# Fri3d_2024_Blaster_00.net
KiCad netlist of a schematic drawn in Altium Designer
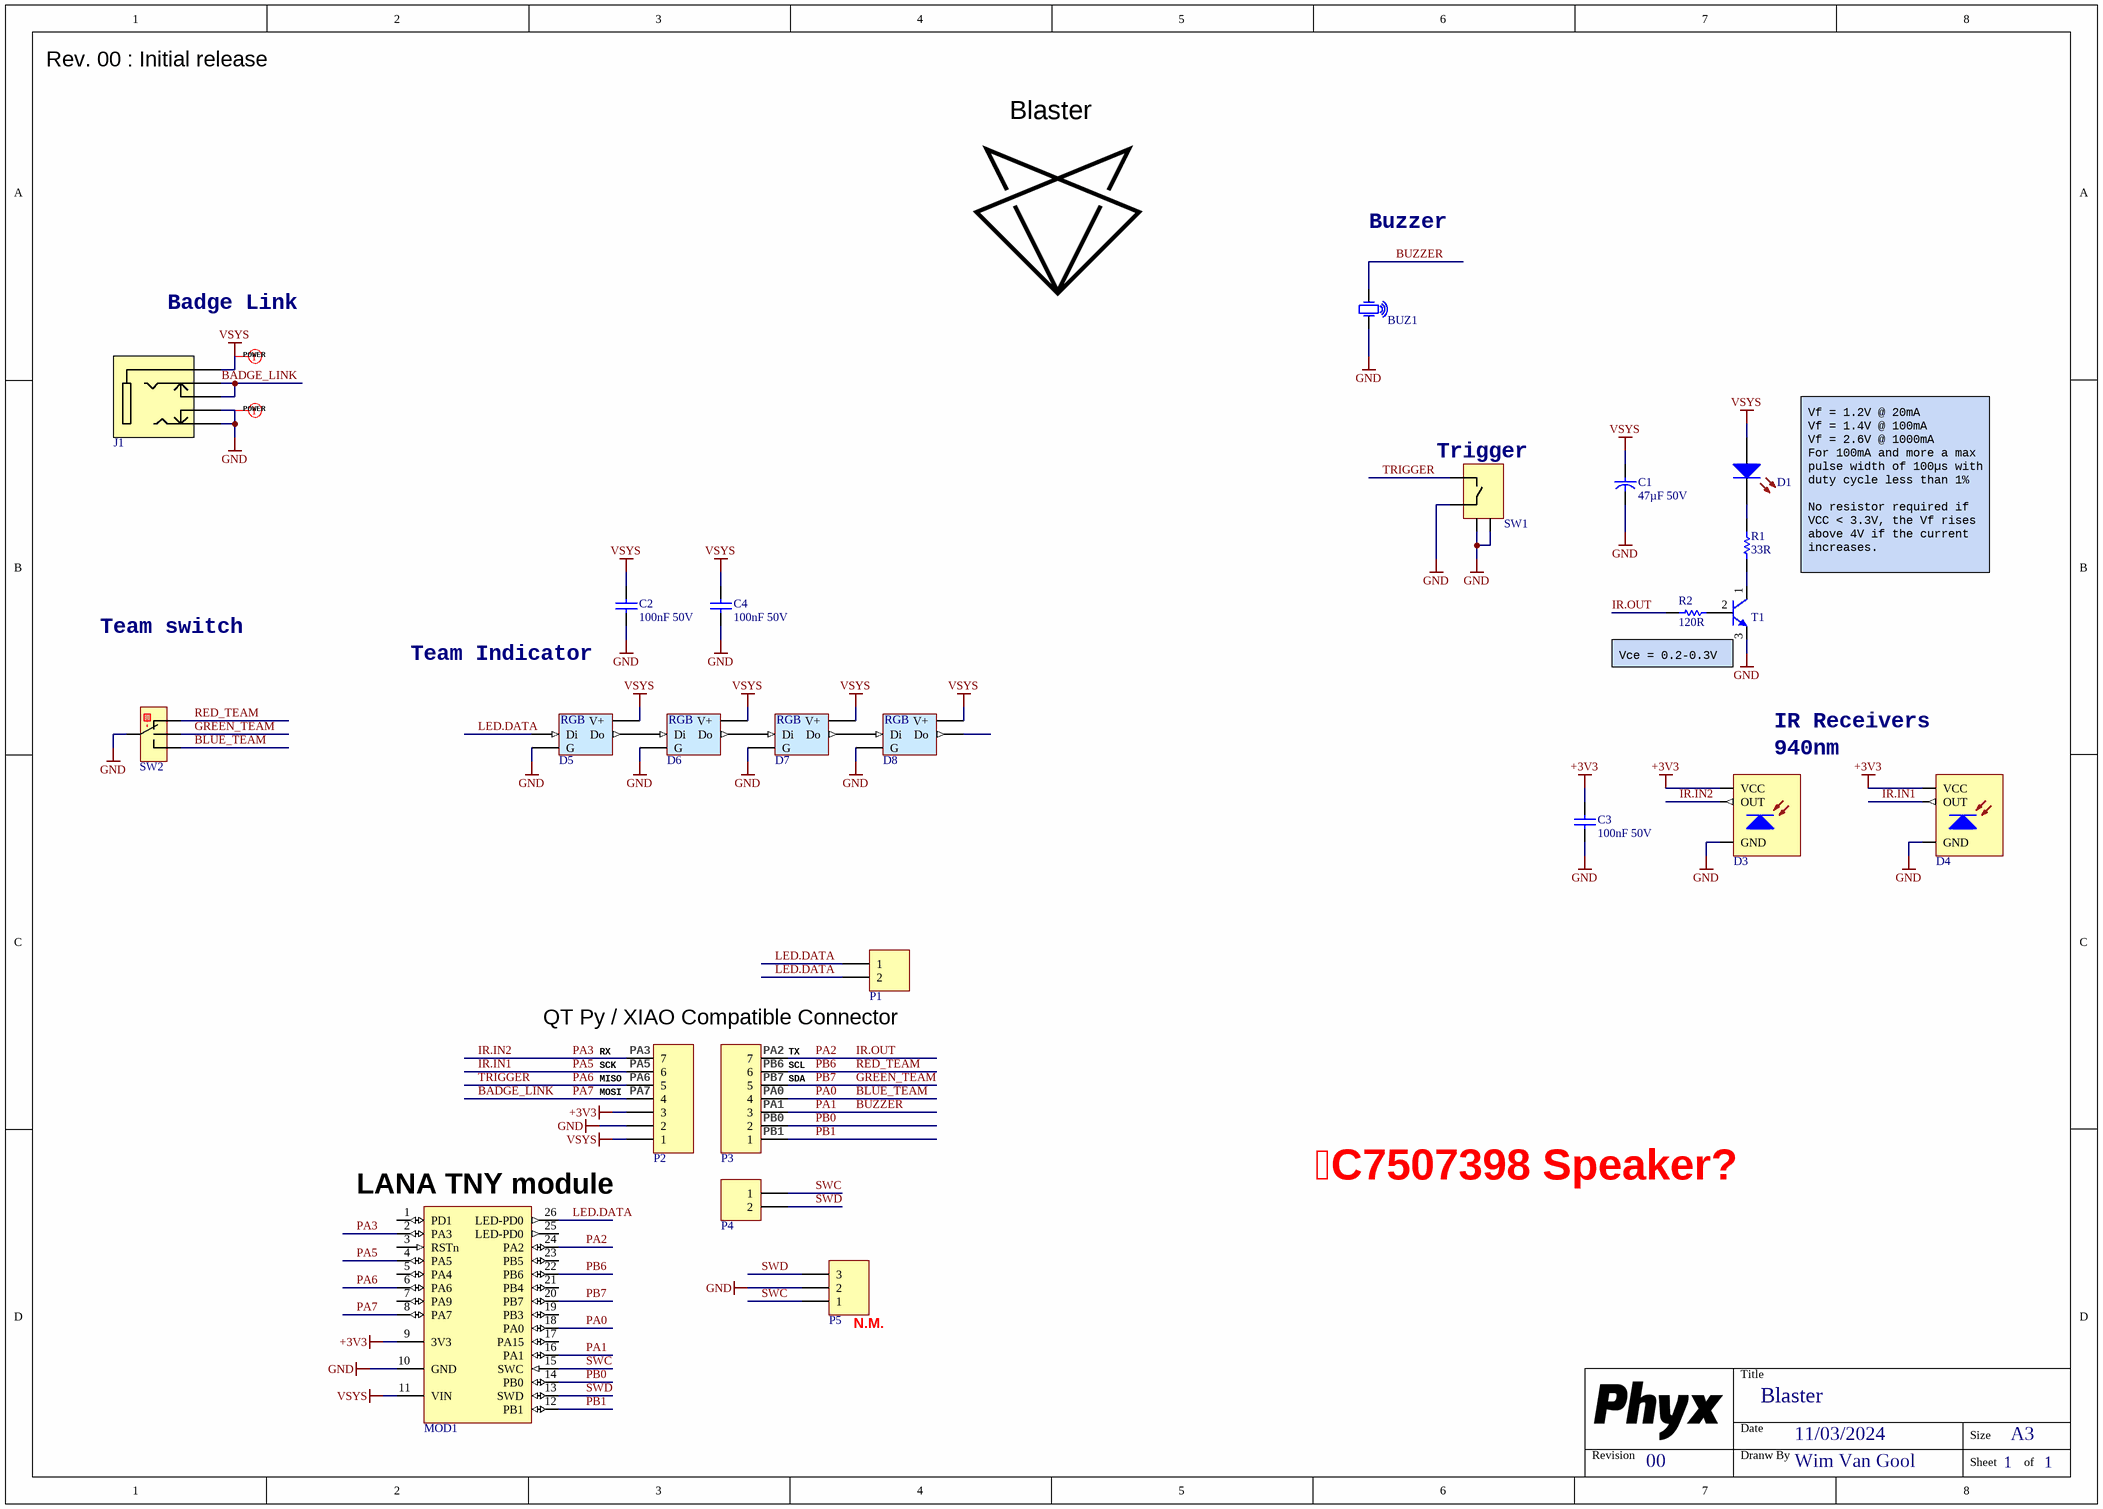
[diagram p0: Fri3d_2024_Blaster_00.SchDoc]

(export (version "E")
  (design (tool "Eeschema 10.0.6"))
  (components
    (comp (ref "BUZ1")
      (value "14x14x7mm Piezo Buzzer Transducer 80dB")
      (footprint "CUI_CEP-1162")
      (description "Crystal Oscillator")
      (libsource (lib "Phyx_Components") (part "Buzzer"))
    )
    (comp (ref "C1")
      (value "47µF 50V")
      (footprint "C_8x9_3.5mm")
      (description "Capacitor electrolyt")
      (fields (field (name "Comment") "CAP_POL"))
      (libsource (lib "Phyx_Components") (part "CAP_POL"))
    )
    (comp (ref "C2")
      (value "100nF 50V")
      (footprint "C_5.08mm")
      (description "Capacitor Ceramic")
      (fields (field (name "Comment") "CAP_CERAMIC"))
      (libsource (lib "Phyx_Components") (part "CAP_CERAMIC"))
    )
    (comp (ref "C3")
      (value "100nF 50V")
      (footprint "C_5.08mm")
      (description "Capacitor Ceramic")
      (fields (field (name "Comment") "CAP_CERAMIC"))
      (libsource (lib "Phyx_Components") (part "CAP_CERAMIC"))
    )
    (comp (ref "C4")
      (value "100nF 50V")
      (footprint "C_5.08mm")
      (description "Capacitor Ceramic")
      (fields (field (name "Comment") "CAP_CERAMIC"))
      (libsource (lib "Phyx_Components") (part "CAP_CERAMIC"))
    )
    (comp (ref "D1")
      (value "5mm IR LED, 940nm, 100mA, 1.35V, 25Deg")
      (footprint "LED_5MM_RD")
      (description "=Description")
      (libsource (lib "Phyx_Components") (part "LED_IR"))
    )
    (comp (ref "D3")
      (value "IRM-3638N3F14 Infrared Receiver 38 kHz 45° 2.7-5.5V")
      (footprint "VIS_TSOP381x_BENT")
      (description "=Description")
      (libsource (lib "Phyx_Components") (part "PHO_IR_TSOP381x"))
    )
    (comp (ref "D4")
      (value "IRM-3638N3F14 Infrared Receiver 38 kHz 45° 2.7-5.5V")
      (footprint "VIS_TSOP381x_BENT")
      (description "=Description")
      (libsource (lib "Phyx_Components") (part "PHO_IR_TSOP381x"))
    )
    (comp (ref "D5")
      (value "WS2812 based digital RGB LED 4020 White package Side emitting")
      (footprint "LED_8mm_RGB_RA")
      (description "=Description")
      (libsource (lib "Phyx_Components") (part "LED_RGB_WS2812B_5mm"))
    )
    (comp (ref "D6")
      (value "WS2812 based digital RGB LED 4020 White package Side emitting")
      (footprint "LED_8mm_RGB_RA")
      (description "=Description")
      (libsource (lib "Phyx_Components") (part "LED_RGB_WS2812B_5mm"))
    )
    (comp (ref "D7")
      (value "WS2812 based digital RGB LED 4020 White package Side emitting")
      (footprint "LED_8mm_RGB_RA")
      (description "=Description")
      (libsource (lib "Phyx_Components") (part "LED_RGB_WS2812B_5mm"))
    )
    (comp (ref "D8")
      (value "WS2812 based digital RGB LED 4020 White package Side emitting")
      (footprint "LED_8mm_RGB_RA")
      (description "=Description")
      (libsource (lib "Phyx_Components") (part "LED_RGB_WS2812B_5mm"))
    )
    (comp (ref "J1")
      (value "3.5mm jack, dual switch, black, 3 contacts")
      (footprint "CUI_SJ1-3525NG")
      (description "=Description")
      (libsource (lib "Phyx_Components") (part "CUI_SJ1-3525NG"))
    )
    (comp (ref "MOD1")
      (value "CH23V203 based TNY module")
      (footprint "PHYX_LANA_TNY_SMD")
      (libsource (lib "Phyx_Components") (part "PHYX_LANA_TNY_SMD"))
    )
    (comp (ref "P1") (value "Header 2") (footprint "HDR1X2") (libsource (lib "") (part "Header 2_1")))
    (comp (ref "P2")
      (value "Header 7")
      (footprint "HDR1X7")
      (libsource (lib "Phyx_Components") (part "Header 7"))
    )
    (comp (ref "P3") (value "Header 7") (footprint "HDR1X7") (libsource (lib "") (part "Header 7_1")))
    (comp (ref "P4")
      (value "Header 2")
      (footprint "HDR1X2")
      (libsource (lib "Phyx_Components") (part "Header 2"))
    )
    (comp (ref "P5")
      (value "Header 3")
      (footprint "HDR1X3")
      (libsource (lib "Phyx_Components") (part "Header 3"))
    )
    (comp (ref "R1")
      (value "33R")
      (footprint "RES_10mm")
      (fields (field (name "Comment") "RESISTOR"))
      (libsource (lib "Phyx_Components") (part "RESISTOR"))
    )
    (comp (ref "R2")
      (value "120R")
      (footprint "RES_10mm")
      (fields (field (name "Comment") "RESISTOR"))
      (libsource (lib "Phyx_Components") (part "RESISTOR"))
    )
    (comp (ref "SW1")
      (value "Tact switch, RA, 3,85mm")
      (footprint "TACTSW_RA_385")
      (libsource (lib "Phyx_Components") (part "SW_TACT_RA"))
    )
    (comp (ref "SW2")
      (value "1P3T SK13D07VG3 3mm post")
      (footprint "SK13D07VG3")
      (libsource (lib "Phyx_Components") (part "SW_1P3T"))
    )
    (comp (ref "T1")
      (value "0.2A 40V 100hfe NPN Transistor")
      (footprint "TO-92A_WIDE")
      (libsource (lib "Phyx_Components") (part "NPN_EBC"))
    )
  )
  (nets
    (net (code "1") (name "+3V3") (class "Default")
      (node (ref "C3") (pin "1") (pinfunction "1_1") (pintype "passive"))
      (node (ref "D3") (pin "3") (pinfunction "VCC_3") (pintype "power_in"))
      (node (ref "D4") (pin "3") (pinfunction "VCC_3") (pintype "power_in"))
      (node (ref "MOD1") (pin "9") (pinfunction "3V3_9") (pintype "power_in"))
      (node (ref "P2") (pin "3") (pinfunction "3_3") (pintype "passive"))
    )
    (net (code "3") (name "/BADGE_LINK") (class "Default")
      (node (ref "J1") (pin "3") (pinfunction "Ring_3") (pintype "passive"))
      (node (ref "J1") (pin "5") (pinfunction "5_5") (pintype "passive"))
      (node (ref "MOD1") (pin "8") (pinfunction "PA7_8") (pintype "bidirectional"))
      (node (ref "P2") (pin "4") (pinfunction "4_4") (pintype "passive"))
    )
    (net (code "4") (name "/BLUE_TEAM") (class "Default")
      (node (ref "MOD1") (pin "18") (pinfunction "PA0_18") (pintype "bidirectional"))
      (node (ref "P3") (pin "4") (pinfunction "4_4") (pintype "passive"))
      (node (ref "SW2") (pin "4") (pinfunction "4_4") (pintype "passive"))
    )
    (net (code "5") (name "/BUZZER") (class "Default")
      (node (ref "BUZ1") (pin "2") (pinfunction "OSC2_2") (pintype "passive"))
      (node (ref "MOD1") (pin "16") (pinfunction "PA1_16") (pintype "bidirectional"))
      (node (ref "P3") (pin "3") (pinfunction "3_3") (pintype "passive"))
    )
    (net (code "6") (name "/GREEN_TEAM") (class "Default")
      (node (ref "MOD1") (pin "20") (pinfunction "PB7_20") (pintype "bidirectional"))
      (node (ref "P3") (pin "5") (pinfunction "5_5") (pintype "passive"))
      (node (ref "SW2") (pin "2") (pinfunction "2_2") (pintype "passive"))
    )
    (net (code "7") (name "/IR.IN1") (class "Default")
      (node (ref "D4") (pin "1") (pinfunction "OUT_1") (pintype "output"))
      (node (ref "MOD1") (pin "4") (pinfunction "PA5_4") (pintype "bidirectional"))
      (node (ref "P2") (pin "6") (pinfunction "6_6") (pintype "passive"))
    )
    (net (code "8") (name "/IR.IN2") (class "Default")
      (node (ref "D3") (pin "1") (pinfunction "OUT_1") (pintype "output"))
      (node (ref "MOD1") (pin "2") (pinfunction "PA3_2") (pintype "bidirectional"))
      (node (ref "P2") (pin "7") (pinfunction "7_7") (pintype "passive"))
    )
    (net (code "9") (name "/IR.OUT") (class "Default")
      (node (ref "MOD1") (pin "24") (pinfunction "PA2_24") (pintype "bidirectional"))
      (node (ref "P3") (pin "7") (pinfunction "7_7") (pintype "passive"))
      (node (ref "R2") (pin "2") (pinfunction "2_2") (pintype "passive"))
    )
    (net (code "10") (name "/LED.DATA") (class "Default")
      (node (ref "D5") (pin "4") (pinfunction "Di_4") (pintype "input"))
      (node (ref "MOD1") (pin "26") (pinfunction "LED-PD0_26") (pintype "output"))
      (node (ref "P1") (pin "1") (pinfunction "1_1") (pintype "passive"))
      (node (ref "P1") (pin "2") (pinfunction "2_2") (pintype "passive"))
    )
    (net (code "11") (name "/PA6") (class "Default")
      (node (ref "MOD1") (pin "6") (pinfunction "PA6_6") (pintype "bidirectional"))
      (node (ref "P2") (pin "5") (pinfunction "5_5") (pintype "passive"))
      (node (ref "SW1") (pin "1") (pinfunction "1_1") (pintype "passive"))
    )
    (net (code "12") (name "/PB0") (class "Default")
      (node (ref "MOD1") (pin "14") (pinfunction "PB0_14") (pintype "bidirectional"))
      (node (ref "P3") (pin "2") (pinfunction "2_2") (pintype "passive"))
    )
    (net (code "13") (name "/PB1") (class "Default")
      (node (ref "MOD1") (pin "12") (pinfunction "PB1_12") (pintype "bidirectional"))
      (node (ref "P3") (pin "1") (pinfunction "1_1") (pintype "passive"))
    )
    (net (code "14") (name "/PB6") (class "Default")
      (node (ref "MOD1") (pin "22") (pinfunction "PB6_22") (pintype "bidirectional"))
      (node (ref "P3") (pin "6") (pinfunction "6_6") (pintype "passive"))
      (node (ref "SW2") (pin "1") (pinfunction "1_1") (pintype "passive"))
    )
    (net (code "15") (name "/SWC") (class "Default")
      (node (ref "MOD1") (pin "15") (pinfunction "SWC_15") (pintype "input"))
      (node (ref "P4") (pin "1") (pinfunction "1_1") (pintype "passive"))
      (node (ref "P5") (pin "1") (pinfunction "1_1") (pintype "passive"))
    )
    (net (code "16") (name "/SWD") (class "Default")
      (node (ref "MOD1") (pin "13") (pinfunction "SWD_13") (pintype "bidirectional"))
      (node (ref "P4") (pin "2") (pinfunction "2_2") (pintype "passive"))
      (node (ref "P5") (pin "3") (pinfunction "3_3") (pintype "passive"))
    )
    (net (code "17") (name "GND") (class "Default")
      (node (ref "BUZ1") (pin "1") (pinfunction "OSC1_1") (pintype "passive"))
      (node (ref "C1") (pin "2") (pinfunction "2_2") (pintype "passive"))
      (node (ref "C2") (pin "2") (pinfunction "2_2") (pintype "passive"))
      (node (ref "C3") (pin "2") (pinfunction "2_2") (pintype "passive"))
      (node (ref "C4") (pin "2") (pinfunction "2_2") (pintype "passive"))
      (node (ref "D3") (pin "2") (pinfunction "GND_2") (pintype "power_in"))
      (node (ref "D4") (pin "2") (pinfunction "GND_2") (pintype "power_in"))
      (node (ref "D5") (pin "3") (pinfunction "G_3") (pintype "power_in"))
      (node (ref "D6") (pin "3") (pinfunction "G_3") (pintype "power_in"))
      (node (ref "D7") (pin "3") (pinfunction "G_3") (pintype "power_in"))
      (node (ref "D8") (pin "3") (pinfunction "G_3") (pintype "power_in"))
      (node (ref "J1") (pin "2") (pinfunction "Tip_2") (pintype "passive"))
      (node (ref "J1") (pin "4") (pinfunction "4_4") (pintype "passive"))
      (node (ref "MOD1") (pin "10") (pinfunction "GND_10") (pintype "power_in"))
      (node (ref "P2") (pin "2") (pinfunction "2_2") (pintype "passive"))
      (node (ref "P5") (pin "2") (pinfunction "2_2") (pintype "passive"))
      (node (ref "SW1") (pin "2") (pinfunction "2_2") (pintype "passive"))
      (node (ref "SW1") (pin "MH1") (pinfunction "MH1_MH1") (pintype "passive"))
      (node (ref "SW1") (pin "MH2") (pinfunction "MH2_MH2") (pintype "passive"))
      (node (ref "SW2") (pin "3") (pinfunction "3_3") (pintype "passive"))
      (node (ref "T1") (pin "3") (pinfunction "E_3") (pintype "passive"))
    )
    (net (code "18") (name "Net-(D1-K)") (class "Default")
      (node (ref "D1") (pin "2") (pinfunction "K_2") (pintype "passive"))
      (node (ref "R1") (pin "1") (pinfunction "1_1") (pintype "passive"))
    )
    (net (code "19") (name "Net-(D5-Do)") (class "Default")
      (node (ref "D5") (pin "1") (pinfunction "Do_1") (pintype "output"))
      (node (ref "D6") (pin "4") (pinfunction "Di_4") (pintype "input"))
    )
    (net (code "20") (name "Net-(D6-Do)") (class "Default")
      (node (ref "D6") (pin "1") (pinfunction "Do_1") (pintype "output"))
      (node (ref "D7") (pin "4") (pinfunction "Di_4") (pintype "input"))
    )
    (net (code "21") (name "Net-(D7-Do)") (class "Default")
      (node (ref "D7") (pin "1") (pinfunction "Do_1") (pintype "output"))
      (node (ref "D8") (pin "4") (pinfunction "Di_4") (pintype "input"))
    )
    (net (code "22") (name "Net-(T1-B)") (class "Default")
      (node (ref "R2") (pin "1") (pinfunction "1_1") (pintype "passive"))
      (node (ref "T1") (pin "2") (pinfunction "B_2") (pintype "passive"))
    )
    (net (code "23") (name "Net-(T1-C)") (class "Default")
      (node (ref "R1") (pin "2") (pinfunction "2_2") (pintype "passive"))
      (node (ref "T1") (pin "1") (pinfunction "C_1") (pintype "passive"))
    )
    (net (code "24") (name "VSYS") (class "Default")
      (node (ref "C1") (pin "1") (pinfunction "1_1") (pintype "passive"))
      (node (ref "C2") (pin "1") (pinfunction "1_1") (pintype "passive"))
      (node (ref "C4") (pin "1") (pinfunction "1_1") (pintype "passive"))
      (node (ref "D1") (pin "1") (pinfunction "A_1") (pintype "passive"))
      (node (ref "D5") (pin "2") (pinfunction "V+_2") (pintype "power_in"))
      (node (ref "D6") (pin "2") (pinfunction "V+_2") (pintype "power_in"))
      (node (ref "D7") (pin "2") (pinfunction "V+_2") (pintype "power_in"))
      (node (ref "D8") (pin "2") (pinfunction "V+_2") (pintype "power_in"))
      (node (ref "J1") (pin "1") (pinfunction "Sleeve_1") (pintype "passive"))
      (node (ref "MOD1") (pin "11") (pinfunction "VIN_11") (pintype "power_in"))
      (node (ref "P2") (pin "1") (pinfunction "1_1") (pintype "passive"))
    )
    (net (code "25") (name "unconnected-(D8-Do-Pad1)") (class "Default")
      (node (ref "D8") (pin "1") (pinfunction "Do_1") (pintype "output"))
    )
    (net (code "26") (name "unconnected-(MOD1-LED-PD0-Pad25)") (class "Default")
      (node (ref "MOD1") (pin "25") (pinfunction "LED-PD0_25") (pintype "output"))
    )
    (net (code "27") (name "unconnected-(MOD1-PA4-Pad5)") (class "Default")
      (node (ref "MOD1") (pin "5") (pinfunction "PA4_5") (pintype "bidirectional"))
    )
    (net (code "28") (name "unconnected-(MOD1-PA9-Pad7)") (class "Default")
      (node (ref "MOD1") (pin "7") (pinfunction "PA9_7") (pintype "bidirectional"))
    )
    (net (code "29") (name "unconnected-(MOD1-PA15-Pad17)") (class "Default")
      (node (ref "MOD1") (pin "17") (pinfunction "PA15_17") (pintype "bidirectional"))
    )
    (net (code "30") (name "unconnected-(MOD1-PB3-Pad19)") (class "Default")
      (node (ref "MOD1") (pin "19") (pinfunction "PB3_19") (pintype "bidirectional"))
    )
    (net (code "31") (name "unconnected-(MOD1-PB4-Pad21)") (class "Default")
      (node (ref "MOD1") (pin "21") (pinfunction "PB4_21") (pintype "bidirectional"))
    )
    (net (code "32") (name "unconnected-(MOD1-PB5-Pad23)") (class "Default")
      (node (ref "MOD1") (pin "23") (pinfunction "PB5_23") (pintype "bidirectional"))
    )
    (net (code "33") (name "unconnected-(MOD1-PD1-Pad1)") (class "Default")
      (node (ref "MOD1") (pin "1") (pinfunction "PD1_1") (pintype "bidirectional"))
    )
    (net (code "34") (name "unconnected-(MOD1-RSTn-Pad3)") (class "Default")
      (node (ref "MOD1") (pin "3") (pinfunction "RSTn_3") (pintype "input"))
    )
  )
)
